# PCA9635_Breadboard.net
KiCad netlist of a schematic drawn in EAGLE
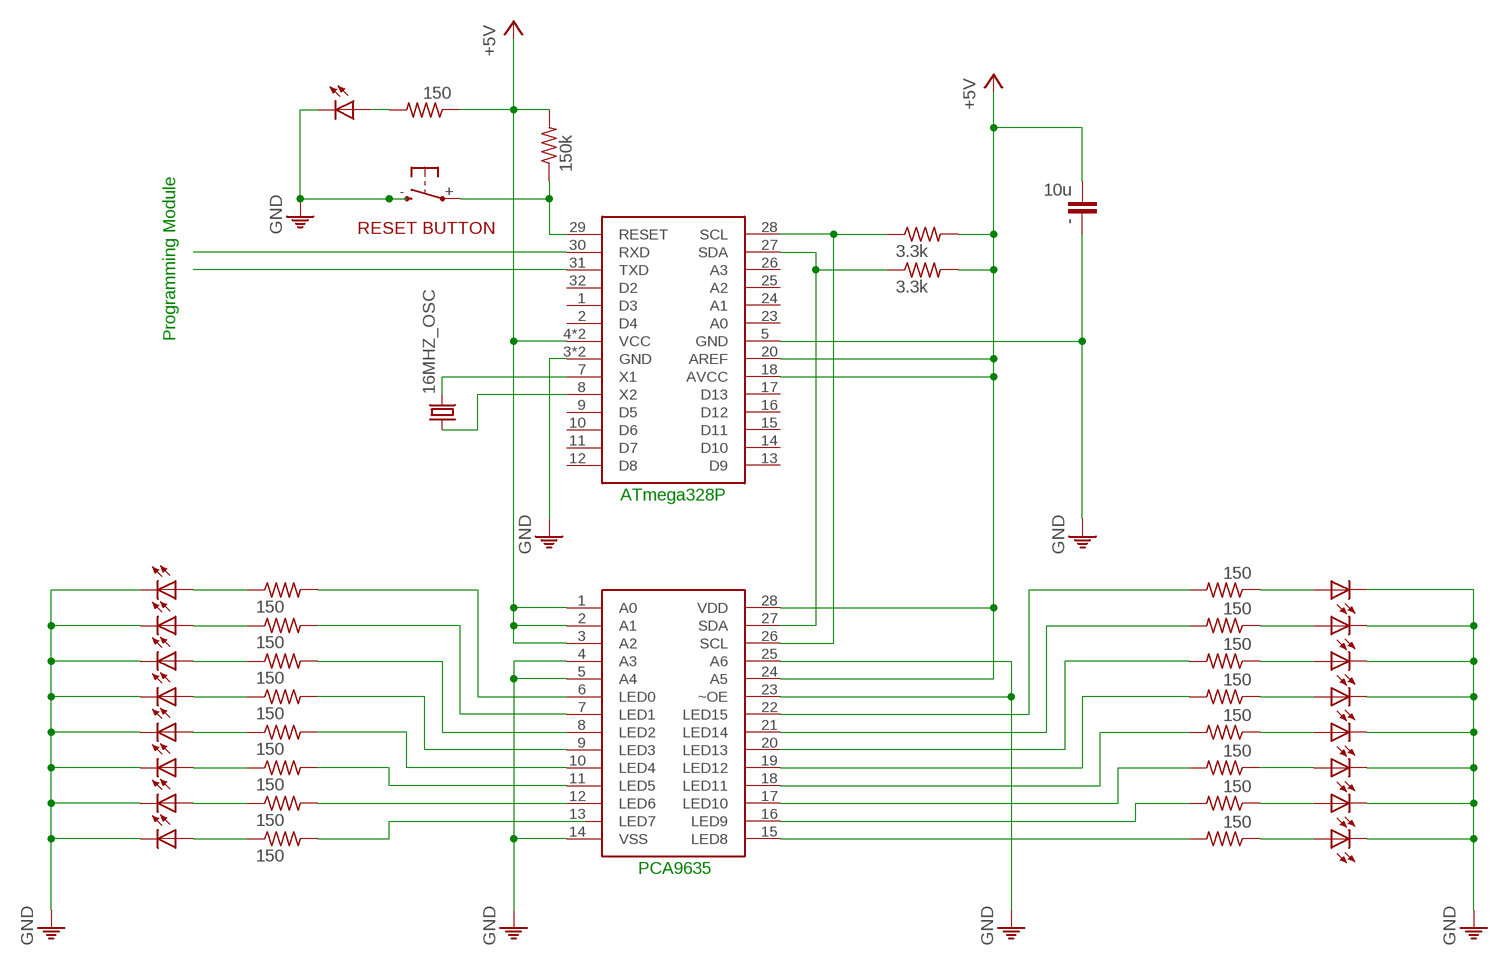
[diagram p0: schematic, sheet 1]

(export (version "E")
  (design (tool "Eeschema 10.0.6"))
  (components
    (comp (ref "'")
      (value "10u")
      (footprint "eagle-import:XC10B6")
      (libsource (lib "eagle-import") (part "CXXC10B6"))
    )
    (comp (ref "16MHZ_OSC")
      (value "CRYSTAL5X3")
      (footprint "eagle-import:CRYSTAL-SMD-5X3")
      (libsource (lib "eagle-import") (part "CRYSTAL5X3"))
    )
    (comp (ref "U$1")
      (value "PCA9635")
      (footprint "eagle-import:TSSOP28")
      (libsource (lib "eagle-import") (part "PCA9635"))
    )
    (comp (ref "U$2")
      (value "ATMEGA328P")
      (footprint "eagle-import:TQFP32-08")
      (libsource (lib "eagle-import") (part "ATMEGA328P"))
    )
    (comp (ref "U$3")
      (value "LED2")
      (footprint "eagle-import:LUMILED")
      (libsource (lib "eagle-import") (part "LED2"))
    )
    (comp (ref "U$4")
      (value "LED2")
      (footprint "eagle-import:LUMILED")
      (libsource (lib "eagle-import") (part "LED2"))
    )
    (comp (ref "U$5")
      (value "LED2")
      (footprint "eagle-import:LUMILED")
      (libsource (lib "eagle-import") (part "LED2"))
    )
    (comp (ref "U$6")
      (value "LED2")
      (footprint "eagle-import:LUMILED")
      (libsource (lib "eagle-import") (part "LED2"))
    )
    (comp (ref "U$7")
      (value "LED2")
      (footprint "eagle-import:LUMILED")
      (libsource (lib "eagle-import") (part "LED2"))
    )
    (comp (ref "U$8")
      (value "LED2")
      (footprint "eagle-import:LUMILED")
      (libsource (lib "eagle-import") (part "LED2"))
    )
    (comp (ref "U$9")
      (value "LED2")
      (footprint "eagle-import:LUMILED")
      (libsource (lib "eagle-import") (part "LED2"))
    )
    (comp (ref "U$10")
      (value "150")
      (footprint "eagle-import:0204_5")
      (libsource (lib "eagle-import") (part "R-US2"))
    )
    (comp (ref "U$11")
      (value "LED2")
      (footprint "eagle-import:LUMILED")
      (libsource (lib "eagle-import") (part "LED2"))
    )
    (comp (ref "U$12")
      (value "150")
      (footprint "eagle-import:0204_5")
      (libsource (lib "eagle-import") (part "R-US2"))
    )
    (comp (ref "U$13")
      (value "150")
      (footprint "eagle-import:0204_5")
      (libsource (lib "eagle-import") (part "R-US2"))
    )
    (comp (ref "U$14")
      (value "150")
      (footprint "eagle-import:0204_5")
      (libsource (lib "eagle-import") (part "R-US2"))
    )
    (comp (ref "U$15")
      (value "150")
      (footprint "eagle-import:0204_5")
      (libsource (lib "eagle-import") (part "R-US2"))
    )
    (comp (ref "U$16")
      (value "150")
      (footprint "eagle-import:0204_5")
      (libsource (lib "eagle-import") (part "R-US2"))
    )
    (comp (ref "U$17")
      (value "150")
      (footprint "eagle-import:0204_5")
      (libsource (lib "eagle-import") (part "R-US2"))
    )
    (comp (ref "U$18")
      (value "150")
      (footprint "eagle-import:0204_5")
      (libsource (lib "eagle-import") (part "R-US2"))
    )
    (comp (ref "U$19")
      (value "LED2")
      (footprint "eagle-import:LUMILED")
      (libsource (lib "eagle-import") (part "LED2"))
    )
    (comp (ref "U$20")
      (value "LED2")
      (footprint "eagle-import:LUMILED")
      (libsource (lib "eagle-import") (part "LED2"))
    )
    (comp (ref "U$21")
      (value "LED2")
      (footprint "eagle-import:LUMILED")
      (libsource (lib "eagle-import") (part "LED2"))
    )
    (comp (ref "U$22")
      (value "LED2")
      (footprint "eagle-import:LUMILED")
      (libsource (lib "eagle-import") (part "LED2"))
    )
    (comp (ref "U$23")
      (value "LED2")
      (footprint "eagle-import:LUMILED")
      (libsource (lib "eagle-import") (part "LED2"))
    )
    (comp (ref "U$24")
      (value "LED2")
      (footprint "eagle-import:LUMILED")
      (libsource (lib "eagle-import") (part "LED2"))
    )
    (comp (ref "U$25")
      (value "LED2")
      (footprint "eagle-import:LUMILED")
      (libsource (lib "eagle-import") (part "LED2"))
    )
    (comp (ref "U$26")
      (value "LED2")
      (footprint "eagle-import:LUMILED")
      (libsource (lib "eagle-import") (part "LED2"))
    )
    (comp (ref "U$27")
      (value "150")
      (footprint "eagle-import:0204_5")
      (libsource (lib "eagle-import") (part "R-US2"))
    )
    (comp (ref "U$28")
      (value "150")
      (footprint "eagle-import:0204_5")
      (libsource (lib "eagle-import") (part "R-US2"))
    )
    (comp (ref "U$29")
      (value "150")
      (footprint "eagle-import:0204_5")
      (libsource (lib "eagle-import") (part "R-US2"))
    )
    (comp (ref "U$30")
      (value "150")
      (footprint "eagle-import:0204_5")
      (libsource (lib "eagle-import") (part "R-US2"))
    )
    (comp (ref "U$31")
      (value "150")
      (footprint "eagle-import:0204_5")
      (libsource (lib "eagle-import") (part "R-US2"))
    )
    (comp (ref "U$32")
      (value "150")
      (footprint "eagle-import:0204_5")
      (libsource (lib "eagle-import") (part "R-US2"))
    )
    (comp (ref "U$33")
      (value "150")
      (footprint "eagle-import:0204_5")
      (libsource (lib "eagle-import") (part "R-US2"))
    )
    (comp (ref "U$34")
      (value "150")
      (footprint "eagle-import:0204_5")
      (libsource (lib "eagle-import") (part "R-US2"))
    )
    (comp (ref "U$35")
      (value "RESET_BUTTON")
      (footprint "eagle-import:DUMMYRESET")
      (libsource (lib "eagle-import") (part "RESET_BUTTON"))
    )
    (comp (ref "U$36")
      (value "150k")
      (footprint "eagle-import:0204_5")
      (libsource (lib "eagle-import") (part "R-US2"))
    )
    (comp (ref "U$38")
      (value "3.3k")
      (footprint "eagle-import:0204_5")
      (libsource (lib "eagle-import") (part "R-US2"))
    )
    (comp (ref "U$40")
      (value "3.3k")
      (footprint "eagle-import:0204_5")
      (libsource (lib "eagle-import") (part "R-US2"))
    )
    (comp (ref "U$41")
      (value "LED2")
      (footprint "eagle-import:LUMILED")
      (libsource (lib "eagle-import") (part "LED2"))
    )
    (comp (ref "U$43")
      (value "150")
      (footprint "eagle-import:0204_5")
      (libsource (lib "eagle-import") (part "R-US2"))
    )
  )
  (nets
    (net (code "1") (name "+5V") (class "Default")
      (node (ref "'") (pin "2") (pinfunction "2_2") (pintype "passive"))
      (node (ref "U$1") (pin "1") (pinfunction "A0_1") (pintype "bidirectional"))
      (node (ref "U$1") (pin "2") (pinfunction "A1_2") (pintype "bidirectional"))
      (node (ref "U$1") (pin "24") (pinfunction "A5_24") (pintype "bidirectional"))
      (node (ref "U$1") (pin "28") (pinfunction "VDD_28") (pintype "bidirectional"))
      (node (ref "U$1") (pin "3") (pinfunction "A2_3") (pintype "bidirectional"))
      (node (ref "U$2") (pin "18") (pinfunction "AVCC_18") (pintype "bidirectional"))
      (node (ref "U$2") (pin "20") (pinfunction "AREF_20") (pintype "bidirectional"))
      (node (ref "U$2") (pin "4") (pinfunction "VCC_4") (pintype "bidirectional"))
      (node (ref "U$2") (pin "6") (pinfunction "VCC_6") (pintype "bidirectional"))
      (node (ref "U$36") (pin "2") (pinfunction "2_2") (pintype "passive"))
      (node (ref "U$38") (pin "2") (pinfunction "2_2") (pintype "passive"))
      (node (ref "U$40") (pin "2") (pinfunction "2_2") (pintype "passive"))
      (node (ref "U$43") (pin "1") (pinfunction "1_1") (pintype "passive"))
    )
    (net (code "2") (name "GND") (class "Default")
      (node (ref "'") (pin "1") (pinfunction "1_1") (pintype "passive"))
      (node (ref "U$1") (pin "14") (pinfunction "VSS_14") (pintype "bidirectional"))
      (node (ref "U$1") (pin "23") (pinfunction "~{OE}_23") (pintype "bidirectional"))
      (node (ref "U$1") (pin "25") (pinfunction "A6_25") (pintype "bidirectional"))
      (node (ref "U$1") (pin "4") (pinfunction "A3_4") (pintype "bidirectional"))
      (node (ref "U$1") (pin "5") (pinfunction "A4_5") (pintype "bidirectional"))
      (node (ref "U$11") (pin "2+") (pinfunction "C_2+") (pintype "passive"))
      (node (ref "U$11") (pin "4-") (pinfunction "C_4-") (pintype "passive"))
      (node (ref "U$19") (pin "2+") (pinfunction "C_2+") (pintype "passive"))
      (node (ref "U$19") (pin "4-") (pinfunction "C_4-") (pintype "passive"))
      (node (ref "U$2") (pin "21") (pinfunction "GND_21") (pintype "bidirectional"))
      (node (ref "U$2") (pin "3") (pinfunction "GND_3") (pintype "bidirectional"))
      (node (ref "U$2") (pin "5") (pinfunction "GND_5") (pintype "bidirectional"))
      (node (ref "U$20") (pin "2+") (pinfunction "C_2+") (pintype "passive"))
      (node (ref "U$20") (pin "4-") (pinfunction "C_4-") (pintype "passive"))
      (node (ref "U$21") (pin "2+") (pinfunction "C_2+") (pintype "passive"))
      (node (ref "U$21") (pin "4-") (pinfunction "C_4-") (pintype "passive"))
      (node (ref "U$22") (pin "2+") (pinfunction "C_2+") (pintype "passive"))
      (node (ref "U$22") (pin "4-") (pinfunction "C_4-") (pintype "passive"))
      (node (ref "U$23") (pin "2+") (pinfunction "C_2+") (pintype "passive"))
      (node (ref "U$23") (pin "4-") (pinfunction "C_4-") (pintype "passive"))
      (node (ref "U$24") (pin "2+") (pinfunction "C_2+") (pintype "passive"))
      (node (ref "U$24") (pin "4-") (pinfunction "C_4-") (pintype "passive"))
      (node (ref "U$25") (pin "2+") (pinfunction "C_2+") (pintype "passive"))
      (node (ref "U$25") (pin "4-") (pinfunction "C_4-") (pintype "passive"))
      (node (ref "U$26") (pin "2+") (pinfunction "C_2+") (pintype "passive"))
      (node (ref "U$26") (pin "4-") (pinfunction "C_4-") (pintype "passive"))
      (node (ref "U$3") (pin "2+") (pinfunction "C_2+") (pintype "passive"))
      (node (ref "U$3") (pin "4-") (pinfunction "C_4-") (pintype "passive"))
      (node (ref "U$35") (pin "-") (pinfunction "3_-") (pintype "passive"))
      (node (ref "U$4") (pin "2+") (pinfunction "C_2+") (pintype "passive"))
      (node (ref "U$4") (pin "4-") (pinfunction "C_4-") (pintype "passive"))
      (node (ref "U$41") (pin "2+") (pinfunction "C_2+") (pintype "passive"))
      (node (ref "U$41") (pin "4-") (pinfunction "C_4-") (pintype "passive"))
      (node (ref "U$5") (pin "2+") (pinfunction "C_2+") (pintype "passive"))
      (node (ref "U$5") (pin "4-") (pinfunction "C_4-") (pintype "passive"))
      (node (ref "U$6") (pin "2+") (pinfunction "C_2+") (pintype "passive"))
      (node (ref "U$6") (pin "4-") (pinfunction "C_4-") (pintype "passive"))
      (node (ref "U$7") (pin "2+") (pinfunction "C_2+") (pintype "passive"))
      (node (ref "U$7") (pin "4-") (pinfunction "C_4-") (pintype "passive"))
      (node (ref "U$8") (pin "2+") (pinfunction "C_2+") (pintype "passive"))
      (node (ref "U$8") (pin "4-") (pinfunction "C_4-") (pintype "passive"))
      (node (ref "U$9") (pin "2+") (pinfunction "C_2+") (pintype "passive"))
      (node (ref "U$9") (pin "4-") (pinfunction "C_4-") (pintype "passive"))
    )
    (net (code "3") (name "Net-(16MHZ_OSC-2)") (class "Default")
      (node (ref "16MHZ_OSC") (pin "3") (pinfunction "2_3") (pintype "passive"))
      (node (ref "U$2") (pin "7") (pinfunction "X1_7") (pintype "bidirectional"))
    )
    (net (code "4") (name "Net-(U$1-LED0)") (class "Default")
      (node (ref "U$1") (pin "6") (pinfunction "LED0_6") (pintype "bidirectional"))
      (node (ref "U$10") (pin "2") (pinfunction "2_2") (pintype "passive"))
    )
    (net (code "5") (name "Net-(U$1-LED1)") (class "Default")
      (node (ref "U$1") (pin "7") (pinfunction "LED1_7") (pintype "bidirectional"))
      (node (ref "U$12") (pin "2") (pinfunction "2_2") (pintype "passive"))
    )
    (net (code "6") (name "Net-(U$1-LED2)") (class "Default")
      (node (ref "U$1") (pin "8") (pinfunction "LED2_8") (pintype "bidirectional"))
      (node (ref "U$13") (pin "2") (pinfunction "2_2") (pintype "passive"))
    )
    (net (code "7") (name "Net-(U$1-LED3)") (class "Default")
      (node (ref "U$1") (pin "9") (pinfunction "LED3_9") (pintype "bidirectional"))
      (node (ref "U$14") (pin "2") (pinfunction "2_2") (pintype "passive"))
    )
    (net (code "8") (name "Net-(U$1-LED4)") (class "Default")
      (node (ref "U$1") (pin "10") (pinfunction "LED4_10") (pintype "bidirectional"))
      (node (ref "U$15") (pin "2") (pinfunction "2_2") (pintype "passive"))
    )
    (net (code "9") (name "Net-(U$1-LED5)") (class "Default")
      (node (ref "U$1") (pin "11") (pinfunction "LED5_11") (pintype "bidirectional"))
      (node (ref "U$16") (pin "2") (pinfunction "2_2") (pintype "passive"))
    )
    (net (code "10") (name "Net-(U$1-LED6)") (class "Default")
      (node (ref "U$1") (pin "12") (pinfunction "LED6_12") (pintype "bidirectional"))
      (node (ref "U$17") (pin "2") (pinfunction "2_2") (pintype "passive"))
    )
    (net (code "11") (name "Net-(U$1-LED8)") (class "Default")
      (node (ref "U$1") (pin "15") (pinfunction "LED8_15") (pintype "bidirectional"))
      (node (ref "U$27") (pin "2") (pinfunction "2_2") (pintype "passive"))
    )
    (net (code "12") (name "Net-(U$1-LED9)") (class "Default")
      (node (ref "U$1") (pin "16") (pinfunction "LED9_16") (pintype "bidirectional"))
      (node (ref "U$28") (pin "2") (pinfunction "2_2") (pintype "passive"))
    )
    (net (code "13") (name "Net-(U$1-LED10)") (class "Default")
      (node (ref "U$1") (pin "17") (pinfunction "LED10_17") (pintype "bidirectional"))
      (node (ref "U$29") (pin "2") (pinfunction "2_2") (pintype "passive"))
    )
    (net (code "14") (name "Net-(U$1-LED11)") (class "Default")
      (node (ref "U$1") (pin "18") (pinfunction "LED11_18") (pintype "bidirectional"))
      (node (ref "U$30") (pin "2") (pinfunction "2_2") (pintype "passive"))
    )
    (net (code "15") (name "Net-(U$1-LED12)") (class "Default")
      (node (ref "U$1") (pin "19") (pinfunction "LED12_19") (pintype "bidirectional"))
      (node (ref "U$31") (pin "2") (pinfunction "2_2") (pintype "passive"))
    )
    (net (code "16") (name "Net-(U$1-LED13)") (class "Default")
      (node (ref "U$1") (pin "20") (pinfunction "LED13_20") (pintype "bidirectional"))
      (node (ref "U$32") (pin "2") (pinfunction "2_2") (pintype "passive"))
    )
    (net (code "17") (name "Net-(U$1-LED14)") (class "Default")
      (node (ref "U$1") (pin "21") (pinfunction "LED14_21") (pintype "bidirectional"))
      (node (ref "U$33") (pin "2") (pinfunction "2_2") (pintype "passive"))
    )
    (net (code "18") (name "Net-(U$1-LED15)") (class "Default")
      (node (ref "U$1") (pin "22") (pinfunction "LED15_22") (pintype "bidirectional"))
      (node (ref "U$34") (pin "2") (pinfunction "2_2") (pintype "passive"))
    )
    (net (code "19") (name "Net-(U$1-SCL)") (class "Default")
      (node (ref "U$1") (pin "26") (pinfunction "SCL_26") (pintype "bidirectional"))
      (node (ref "U$2") (pin "28") (pinfunction "SCL_28") (pintype "bidirectional"))
      (node (ref "U$40") (pin "1") (pinfunction "1_1") (pintype "passive"))
    )
    (net (code "20") (name "Net-(U$1-SDA)") (class "Default")
      (node (ref "U$1") (pin "27") (pinfunction "SDA_27") (pintype "bidirectional"))
      (node (ref "U$2") (pin "27") (pinfunction "SDA_27") (pintype "bidirectional"))
      (node (ref "U$38") (pin "1") (pinfunction "1_1") (pintype "passive"))
    )
    (net (code "21") (name "Net-(U$2-RESET)") (class "Default")
      (node (ref "U$2") (pin "29") (pinfunction "RESET_29") (pintype "bidirectional"))
      (node (ref "U$35") (pin "+") (pinfunction "1_+") (pintype "passive"))
      (node (ref "U$36") (pin "1") (pinfunction "1_1") (pintype "passive"))
    )
    (net (code "22") (name "Net-(U$2-X2)") (class "Default")
      (node (ref "16MHZ_OSC") (pin "1") (pinfunction "1_1") (pintype "passive"))
      (node (ref "U$2") (pin "8") (pinfunction "X2_8") (pintype "bidirectional"))
    )
    (net (code "23") (name "Net-(U$10-Pad1)") (class "Default")
      (node (ref "U$10") (pin "1") (pinfunction "1_1") (pintype "passive"))
      (node (ref "U$3") (pin "1NC") (pinfunction "A_1NC") (pintype "passive"))
      (node (ref "U$3") (pin "3NC") (pinfunction "A_3NC") (pintype "passive"))
    )
    (net (code "24") (name "Net-(U$11-A-Pad1NC)") (class "Default")
      (node (ref "U$11") (pin "1NC") (pinfunction "A_1NC") (pintype "passive"))
      (node (ref "U$11") (pin "3NC") (pinfunction "A_3NC") (pintype "passive"))
      (node (ref "U$18") (pin "1") (pinfunction "1_1") (pintype "passive"))
    )
    (net (code "25") (name "Net-(U$12-Pad1)") (class "Default")
      (node (ref "U$12") (pin "1") (pinfunction "1_1") (pintype "passive"))
      (node (ref "U$4") (pin "1NC") (pinfunction "A_1NC") (pintype "passive"))
      (node (ref "U$4") (pin "3NC") (pinfunction "A_3NC") (pintype "passive"))
    )
    (net (code "26") (name "Net-(U$13-Pad1)") (class "Default")
      (node (ref "U$13") (pin "1") (pinfunction "1_1") (pintype "passive"))
      (node (ref "U$5") (pin "1NC") (pinfunction "A_1NC") (pintype "passive"))
      (node (ref "U$5") (pin "3NC") (pinfunction "A_3NC") (pintype "passive"))
    )
    (net (code "27") (name "Net-(U$14-Pad1)") (class "Default")
      (node (ref "U$14") (pin "1") (pinfunction "1_1") (pintype "passive"))
      (node (ref "U$6") (pin "1NC") (pinfunction "A_1NC") (pintype "passive"))
      (node (ref "U$6") (pin "3NC") (pinfunction "A_3NC") (pintype "passive"))
    )
    (net (code "28") (name "Net-(U$15-Pad1)") (class "Default")
      (node (ref "U$15") (pin "1") (pinfunction "1_1") (pintype "passive"))
      (node (ref "U$7") (pin "1NC") (pinfunction "A_1NC") (pintype "passive"))
      (node (ref "U$7") (pin "3NC") (pinfunction "A_3NC") (pintype "passive"))
    )
    (net (code "29") (name "Net-(U$16-Pad1)") (class "Default")
      (node (ref "U$16") (pin "1") (pinfunction "1_1") (pintype "passive"))
      (node (ref "U$8") (pin "1NC") (pinfunction "A_1NC") (pintype "passive"))
      (node (ref "U$8") (pin "3NC") (pinfunction "A_3NC") (pintype "passive"))
    )
    (net (code "30") (name "Net-(U$17-Pad1)") (class "Default")
      (node (ref "U$17") (pin "1") (pinfunction "1_1") (pintype "passive"))
      (node (ref "U$9") (pin "1NC") (pinfunction "A_1NC") (pintype "passive"))
      (node (ref "U$9") (pin "3NC") (pinfunction "A_3NC") (pintype "passive"))
    )
    (net (code "31") (name "Net-(U$19-A-Pad1NC)") (class "Default")
      (node (ref "U$19") (pin "1NC") (pinfunction "A_1NC") (pintype "passive"))
      (node (ref "U$19") (pin "3NC") (pinfunction "A_3NC") (pintype "passive"))
      (node (ref "U$27") (pin "1") (pinfunction "1_1") (pintype "passive"))
    )
    (net (code "32") (name "Net-(U$20-A-Pad1NC)") (class "Default")
      (node (ref "U$20") (pin "1NC") (pinfunction "A_1NC") (pintype "passive"))
      (node (ref "U$20") (pin "3NC") (pinfunction "A_3NC") (pintype "passive"))
      (node (ref "U$28") (pin "1") (pinfunction "1_1") (pintype "passive"))
    )
    (net (code "33") (name "Net-(U$21-A-Pad1NC)") (class "Default")
      (node (ref "U$21") (pin "1NC") (pinfunction "A_1NC") (pintype "passive"))
      (node (ref "U$21") (pin "3NC") (pinfunction "A_3NC") (pintype "passive"))
      (node (ref "U$29") (pin "1") (pinfunction "1_1") (pintype "passive"))
    )
    (net (code "34") (name "Net-(U$22-A-Pad1NC)") (class "Default")
      (node (ref "U$22") (pin "1NC") (pinfunction "A_1NC") (pintype "passive"))
      (node (ref "U$22") (pin "3NC") (pinfunction "A_3NC") (pintype "passive"))
      (node (ref "U$30") (pin "1") (pinfunction "1_1") (pintype "passive"))
    )
    (net (code "35") (name "Net-(U$23-A-Pad1NC)") (class "Default")
      (node (ref "U$23") (pin "1NC") (pinfunction "A_1NC") (pintype "passive"))
      (node (ref "U$23") (pin "3NC") (pinfunction "A_3NC") (pintype "passive"))
      (node (ref "U$31") (pin "1") (pinfunction "1_1") (pintype "passive"))
    )
    (net (code "36") (name "Net-(U$24-A-Pad1NC)") (class "Default")
      (node (ref "U$24") (pin "1NC") (pinfunction "A_1NC") (pintype "passive"))
      (node (ref "U$24") (pin "3NC") (pinfunction "A_3NC") (pintype "passive"))
      (node (ref "U$32") (pin "1") (pinfunction "1_1") (pintype "passive"))
    )
    (net (code "37") (name "Net-(U$25-A-Pad1NC)") (class "Default")
      (node (ref "U$25") (pin "1NC") (pinfunction "A_1NC") (pintype "passive"))
      (node (ref "U$25") (pin "3NC") (pinfunction "A_3NC") (pintype "passive"))
      (node (ref "U$33") (pin "1") (pinfunction "1_1") (pintype "passive"))
    )
    (net (code "38") (name "Net-(U$26-A-Pad1NC)") (class "Default")
      (node (ref "U$26") (pin "1NC") (pinfunction "A_1NC") (pintype "passive"))
      (node (ref "U$26") (pin "3NC") (pinfunction "A_3NC") (pintype "passive"))
      (node (ref "U$34") (pin "1") (pinfunction "1_1") (pintype "passive"))
    )
    (net (code "39") (name "Net-(U$41-A-Pad1NC)") (class "Default")
      (node (ref "U$41") (pin "1NC") (pinfunction "A_1NC") (pintype "passive"))
      (node (ref "U$41") (pin "3NC") (pinfunction "A_3NC") (pintype "passive"))
      (node (ref "U$43") (pin "2") (pinfunction "2_2") (pintype "passive"))
    )
    (net (code "40") (name "unconnected-(U$1-LED7-Pad13)") (class "Default")
      (node (ref "U$1") (pin "13") (pinfunction "LED7_13") (pintype "bidirectional"))
    )
    (net (code "41") (name "unconnected-(U$2-A0-Pad23)") (class "Default")
      (node (ref "U$2") (pin "23") (pinfunction "A0_23") (pintype "bidirectional"))
    )
    (net (code "42") (name "unconnected-(U$2-A1-Pad24)") (class "Default")
      (node (ref "U$2") (pin "24") (pinfunction "A1_24") (pintype "bidirectional"))
    )
    (net (code "43") (name "unconnected-(U$2-A2-Pad25)") (class "Default")
      (node (ref "U$2") (pin "25") (pinfunction "A2_25") (pintype "bidirectional"))
    )
    (net (code "44") (name "unconnected-(U$2-A3-Pad26)") (class "Default")
      (node (ref "U$2") (pin "26") (pinfunction "A3_26") (pintype "bidirectional"))
    )
    (net (code "45") (name "unconnected-(U$2-D2-Pad32)") (class "Default")
      (node (ref "U$2") (pin "32") (pinfunction "D2_32") (pintype "bidirectional"))
    )
    (net (code "46") (name "unconnected-(U$2-D3-Pad1)") (class "Default")
      (node (ref "U$2") (pin "1") (pinfunction "D3_1") (pintype "bidirectional"))
    )
    (net (code "47") (name "unconnected-(U$2-D4-Pad2)") (class "Default")
      (node (ref "U$2") (pin "2") (pinfunction "D4_2") (pintype "bidirectional"))
    )
    (net (code "48") (name "unconnected-(U$2-D5-Pad9)") (class "Default")
      (node (ref "U$2") (pin "9") (pinfunction "D5_9") (pintype "bidirectional"))
    )
    (net (code "49") (name "unconnected-(U$2-D6-Pad10)") (class "Default")
      (node (ref "U$2") (pin "10") (pinfunction "D6_10") (pintype "bidirectional"))
    )
    (net (code "50") (name "unconnected-(U$2-D7-Pad11)") (class "Default")
      (node (ref "U$2") (pin "11") (pinfunction "D7_11") (pintype "bidirectional"))
    )
    (net (code "51") (name "unconnected-(U$2-D8-Pad12)") (class "Default")
      (node (ref "U$2") (pin "12") (pinfunction "D8_12") (pintype "bidirectional"))
    )
    (net (code "52") (name "unconnected-(U$2-D9-Pad13)") (class "Default")
      (node (ref "U$2") (pin "13") (pinfunction "D9_13") (pintype "bidirectional"))
    )
    (net (code "53") (name "unconnected-(U$2-D10-Pad14)") (class "Default")
      (node (ref "U$2") (pin "14") (pinfunction "D10_14") (pintype "bidirectional"))
    )
    (net (code "54") (name "unconnected-(U$2-D11-Pad15)") (class "Default")
      (node (ref "U$2") (pin "15") (pinfunction "D11_15") (pintype "bidirectional"))
    )
    (net (code "55") (name "unconnected-(U$2-D12-Pad16)") (class "Default")
      (node (ref "U$2") (pin "16") (pinfunction "D12_16") (pintype "bidirectional"))
    )
    (net (code "56") (name "unconnected-(U$2-D13-Pad17)") (class "Default")
      (node (ref "U$2") (pin "17") (pinfunction "D13_17") (pintype "bidirectional"))
    )
    (net (code "57") (name "unconnected-(U$2-RXD-Pad30)") (class "Default")
      (node (ref "U$2") (pin "30") (pinfunction "RXD_30") (pintype "bidirectional"))
    )
    (net (code "58") (name "unconnected-(U$2-TXD-Pad31)") (class "Default")
      (node (ref "U$2") (pin "31") (pinfunction "TXD_31") (pintype "bidirectional"))
    )
    (net (code "59") (name "unconnected-(U$18-Pad2)") (class "Default")
      (node (ref "U$18") (pin "2") (pinfunction "2_2") (pintype "passive"))
    )
  )
)
